# forest21.net
KiCad netlist of a schematic drawn in EAGLE
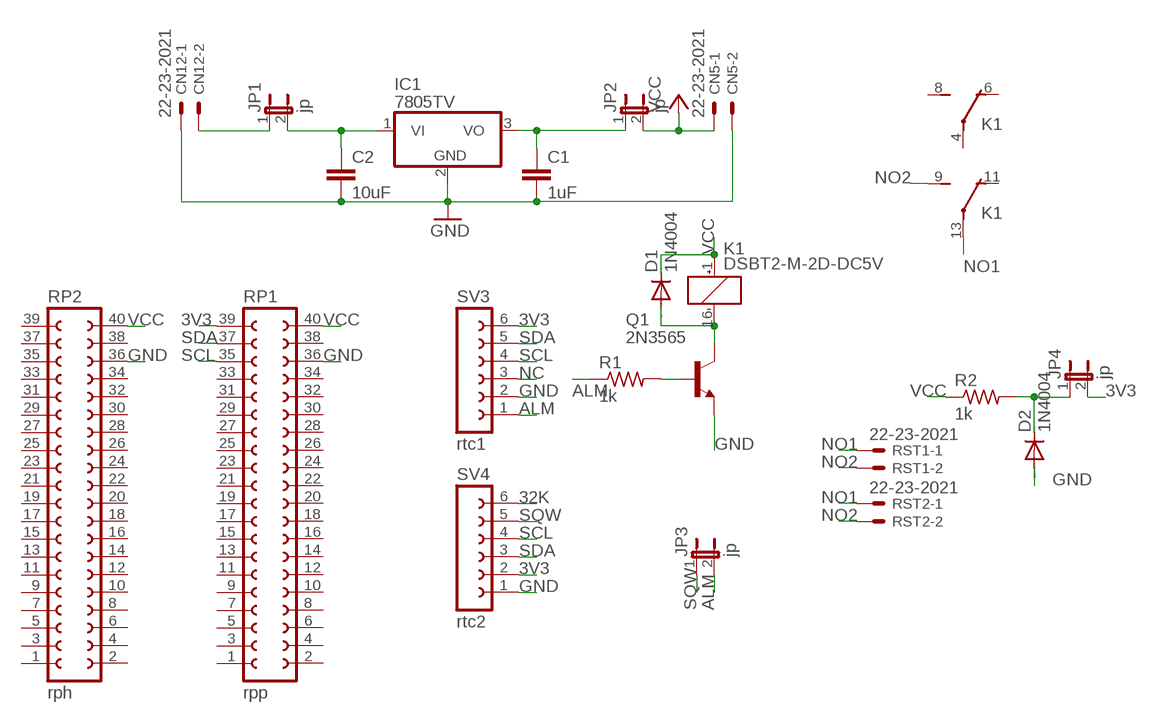
[diagram p0: schematic, sheet 1]

(export (version "E")
  (design (tool "Eeschema 10.0.6"))
  (components
    (comp (ref "C1")
      (value "1uF")
      (footprint "eagle-import:C025-030X050")
      (libsource (lib "eagle-import") (part "C-EU025-030X050"))
    )
    (comp (ref "C2")
      (value "10uF")
      (footprint "eagle-import:C025-030X050")
      (libsource (lib "eagle-import") (part "C-EU025-030X050"))
    )
    (comp (ref "CN5")
      (value "22-23-2021")
      (footprint "eagle-import:22-23-2021")
      (fields (field (name "MF") "MOLEX"))
      (libsource (lib "eagle-import") (part "22-23-2021"))
    )
    (comp (ref "CN12")
      (value "22-23-2021")
      (footprint "eagle-import:22-23-2021")
      (fields (field (name "MF") "MOLEX"))
      (libsource (lib "eagle-import") (part "22-23-2021"))
    )
    (comp (ref "D1")
      (value "1N4004")
      (footprint "eagle-import:DO41-10")
      (libsource (lib "eagle-import") (part "1N4004"))
    )
    (comp (ref "D2")
      (value "1N4004")
      (footprint "eagle-import:DO41-10")
      (libsource (lib "eagle-import") (part "1N4004"))
    )
    (comp (ref "IC1")
      (value "7805TV")
      (footprint "eagle-import:TO220V")
      (libsource (lib "eagle-import") (part "78TV05"))
    )
    (comp (ref "JP1")
      (value "jp")
      (footprint "eagle-import:JP1")
      (libsource (lib "eagle-import") (part "JP1E"))
    )
    (comp (ref "JP2")
      (value "jp")
      (footprint "eagle-import:JP1")
      (libsource (lib "eagle-import") (part "JP1E"))
    )
    (comp (ref "JP3")
      (value "jp")
      (footprint "eagle-import:JP1")
      (libsource (lib "eagle-import") (part "JP1E"))
    )
    (comp (ref "JP4")
      (value "jp")
      (footprint "eagle-import:JP1")
      (libsource (lib "eagle-import") (part "JP1E"))
    )
    (comp (ref "K1")
      (value "DSBT2-M-2D-DC5V")
      (footprint "eagle-import:DS-BT")
      (libsource (lib "eagle-import") (part "DSBT2-M-2D-DC5V"))
    )
    (comp (ref "Q1")
      (value "2N3565")
      (footprint "eagle-import:TO92")
      (libsource (lib "eagle-import") (part "2N3565"))
    )
    (comp (ref "R1")
      (value "1k")
      (footprint "eagle-import:0207_7")
      (libsource (lib "eagle-import") (part "R-US_0207/7"))
    )
    (comp (ref "R2")
      (value "1k")
      (footprint "eagle-import:0207_7")
      (libsource (lib "eagle-import") (part "R-US_0207/7"))
    )
    (comp (ref "RP1")
      (value "rpp")
      (footprint "eagle-import:FE20-2")
      (libsource (lib "eagle-import") (part "FE20-2"))
    )
    (comp (ref "RP2")
      (value "rph")
      (footprint "eagle-import:FE20-2")
      (libsource (lib "eagle-import") (part "FE20-2"))
    )
    (comp (ref "RST1")
      (value "22-23-2021")
      (footprint "eagle-import:22-23-2021")
      (fields (field (name "MF") "MOLEX"))
      (libsource (lib "eagle-import") (part "22-23-2021"))
    )
    (comp (ref "RST2")
      (value "22-23-2021")
      (footprint "eagle-import:22-23-2021")
      (fields (field (name "MF") "MOLEX"))
      (libsource (lib "eagle-import") (part "22-23-2021"))
    )
    (comp (ref "SV3")
      (value "rtc1")
      (footprint "eagle-import:FE06")
      (libsource (lib "eagle-import") (part "FE06-1"))
    )
    (comp (ref "SV4")
      (value "rtc2")
      (footprint "eagle-import:FE06")
      (libsource (lib "eagle-import") (part "FE06-1"))
    )
  )
  (nets
    (net (code "1") (name "/3V3") (class "Default")
      (node (ref "JP4") (pin "2") (pinfunction "2_2") (pintype "passive"))
      (node (ref "RP1") (pin "39") (pinfunction "39_39") (pintype "passive"))
      (node (ref "SV3") (pin "6") (pinfunction "6_6") (pintype "passive"))
      (node (ref "SV4") (pin "2") (pinfunction "2_2") (pintype "passive"))
    )
    (net (code "2") (name "/32K") (class "Default")
      (node (ref "SV4") (pin "6") (pinfunction "6_6") (pintype "passive"))
    )
    (net (code "3") (name "/ALM") (class "Default")
      (node (ref "JP3") (pin "2") (pinfunction "2_2") (pintype "passive"))
      (node (ref "R1") (pin "1") (pinfunction "1_1") (pintype "passive"))
      (node (ref "SV3") (pin "1") (pinfunction "1_1") (pintype "passive"))
    )
    (net (code "4") (name "/NC") (class "Default")
      (node (ref "SV3") (pin "3") (pinfunction "3_3") (pintype "passive"))
    )
    (net (code "5") (name "/NO1") (class "Default")
      (node (ref "K1") (pin "13") (pinfunction "P_13") (pintype "passive"))
      (node (ref "RST1") (pin "1") (pinfunction "S_1") (pintype "passive"))
      (node (ref "RST2") (pin "1") (pinfunction "S_1") (pintype "passive"))
    )
    (net (code "6") (name "/NO2") (class "Default")
      (node (ref "K1") (pin "9") (pinfunction "S_9") (pintype "passive"))
      (node (ref "RST1") (pin "2") (pinfunction "S_2") (pintype "passive"))
      (node (ref "RST2") (pin "2") (pinfunction "S_2") (pintype "passive"))
    )
    (net (code "7") (name "/SCL") (class "Default")
      (node (ref "RP1") (pin "35") (pinfunction "35_35") (pintype "passive"))
      (node (ref "SV3") (pin "4") (pinfunction "4_4") (pintype "passive"))
      (node (ref "SV4") (pin "4") (pinfunction "4_4") (pintype "passive"))
    )
    (net (code "8") (name "/SDA") (class "Default")
      (node (ref "RP1") (pin "37") (pinfunction "37_37") (pintype "passive"))
      (node (ref "SV3") (pin "5") (pinfunction "5_5") (pintype "passive"))
      (node (ref "SV4") (pin "3") (pinfunction "3_3") (pintype "passive"))
    )
    (net (code "9") (name "/SQW") (class "Default")
      (node (ref "JP3") (pin "1") (pinfunction "1_1") (pintype "passive"))
      (node (ref "SV4") (pin "5") (pinfunction "5_5") (pintype "passive"))
    )
    (net (code "10") (name "GND") (class "Default")
      (node (ref "C1") (pin "2") (pinfunction "2_2") (pintype "passive"))
      (node (ref "C2") (pin "2") (pinfunction "2_2") (pintype "passive"))
      (node (ref "CN12") (pin "1") (pinfunction "S_1") (pintype "passive"))
      (node (ref "CN5") (pin "2") (pinfunction "S_2") (pintype "passive"))
      (node (ref "D2") (pin "A") (pinfunction "A_A") (pintype "passive"))
      (node (ref "IC1") (pin "2") (pinfunction "GND_2") (pintype "passive"))
      (node (ref "Q1") (pin "3") (pinfunction "E_3") (pintype "passive"))
      (node (ref "RP1") (pin "36") (pinfunction "36_36") (pintype "passive"))
      (node (ref "RP2") (pin "36") (pinfunction "36_36") (pintype "passive"))
      (node (ref "SV3") (pin "2") (pinfunction "2_2") (pintype "passive"))
      (node (ref "SV4") (pin "1") (pinfunction "1_1") (pintype "passive"))
    )
    (net (code "11") (name "Net-(CN12B-S)") (class "Default")
      (node (ref "CN12") (pin "2") (pinfunction "S_2") (pintype "passive"))
      (node (ref "JP1") (pin "1") (pinfunction "1_1") (pintype "passive"))
    )
    (net (code "12") (name "Net-(D2-PadC)") (class "Default")
      (node (ref "D2") (pin "C") (pinfunction "C_C") (pintype "passive"))
      (node (ref "JP4") (pin "1") (pinfunction "1_1") (pintype "passive"))
      (node (ref "R2") (pin "2") (pinfunction "2_2") (pintype "passive"))
    )
    (net (code "13") (name "Net-(IC1-VI)") (class "Default")
      (node (ref "C2") (pin "1") (pinfunction "1_1") (pintype "passive"))
      (node (ref "IC1") (pin "1") (pinfunction "VI_1") (pintype "input"))
      (node (ref "JP1") (pin "2") (pinfunction "2_2") (pintype "passive"))
    )
    (net (code "14") (name "Net-(IC1-VO)") (class "Default")
      (node (ref "C1") (pin "1") (pinfunction "1_1") (pintype "passive"))
      (node (ref "IC1") (pin "3") (pinfunction "VO_3") (pintype "passive"))
      (node (ref "JP2") (pin "1") (pinfunction "1_1") (pintype "passive"))
    )
    (net (code "15") (name "Net-(K1A--)") (class "Default")
      (node (ref "D1") (pin "A") (pinfunction "A_A") (pintype "passive"))
      (node (ref "K1") (pin "16") (pinfunction "-_16") (pintype "passive"))
      (node (ref "Q1") (pin "1") (pinfunction "C_1") (pintype "passive"))
    )
    (net (code "16") (name "Net-(Q1-B)") (class "Default")
      (node (ref "Q1") (pin "2") (pinfunction "B_2") (pintype "passive"))
      (node (ref "R1") (pin "2") (pinfunction "2_2") (pintype "passive"))
    )
    (net (code "17") (name "VCC") (class "Default")
      (node (ref "CN5") (pin "1") (pinfunction "S_1") (pintype "passive"))
      (node (ref "D1") (pin "C") (pinfunction "C_C") (pintype "passive"))
      (node (ref "JP2") (pin "2") (pinfunction "2_2") (pintype "passive"))
      (node (ref "K1") (pin "1") (pinfunction "+_1") (pintype "passive"))
      (node (ref "R2") (pin "1") (pinfunction "1_1") (pintype "passive"))
      (node (ref "RP1") (pin "40") (pinfunction "40_40") (pintype "passive"))
      (node (ref "RP2") (pin "40") (pinfunction "40_40") (pintype "passive"))
    )
    (net (code "18") (name "unconnected-(K1B-O-Pad6)") (class "Default")
      (node (ref "K1") (pin "6") (pinfunction "O_6") (pintype "passive"))
    )
    (net (code "19") (name "unconnected-(K1B-P-Pad4)") (class "Default")
      (node (ref "K1") (pin "4") (pinfunction "P_4") (pintype "passive"))
    )
    (net (code "20") (name "unconnected-(K1B-S-Pad8)") (class "Default")
      (node (ref "K1") (pin "8") (pinfunction "S_8") (pintype "passive"))
    )
    (net (code "21") (name "unconnected-(K1C-O-Pad11)") (class "Default")
      (node (ref "K1") (pin "11") (pinfunction "O_11") (pintype "passive"))
    )
    (net (code "22") (name "unconnected-(RP1-Pad1)") (class "Default")
      (node (ref "RP1") (pin "1") (pinfunction "1_1") (pintype "passive"))
    )
    (net (code "23") (name "unconnected-(RP1-Pad2)") (class "Default")
      (node (ref "RP1") (pin "2") (pinfunction "2_2") (pintype "passive"))
    )
    (net (code "24") (name "unconnected-(RP1-Pad3)") (class "Default")
      (node (ref "RP1") (pin "3") (pinfunction "3_3") (pintype "passive"))
    )
    (net (code "25") (name "unconnected-(RP1-Pad4)") (class "Default")
      (node (ref "RP1") (pin "4") (pinfunction "4_4") (pintype "passive"))
    )
    (net (code "26") (name "unconnected-(RP1-Pad5)") (class "Default")
      (node (ref "RP1") (pin "5") (pinfunction "5_5") (pintype "passive"))
    )
    (net (code "27") (name "unconnected-(RP1-Pad6)") (class "Default")
      (node (ref "RP1") (pin "6") (pinfunction "6_6") (pintype "passive"))
    )
    (net (code "28") (name "unconnected-(RP1-Pad7)") (class "Default")
      (node (ref "RP1") (pin "7") (pinfunction "7_7") (pintype "passive"))
    )
    (net (code "29") (name "unconnected-(RP1-Pad8)") (class "Default")
      (node (ref "RP1") (pin "8") (pinfunction "8_8") (pintype "passive"))
    )
    (net (code "30") (name "unconnected-(RP1-Pad9)") (class "Default")
      (node (ref "RP1") (pin "9") (pinfunction "9_9") (pintype "passive"))
    )
    (net (code "31") (name "unconnected-(RP1-Pad10)") (class "Default")
      (node (ref "RP1") (pin "10") (pinfunction "10_10") (pintype "passive"))
    )
    (net (code "32") (name "unconnected-(RP1-Pad11)") (class "Default")
      (node (ref "RP1") (pin "11") (pinfunction "11_11") (pintype "passive"))
    )
    (net (code "33") (name "unconnected-(RP1-Pad12)") (class "Default")
      (node (ref "RP1") (pin "12") (pinfunction "12_12") (pintype "passive"))
    )
    (net (code "34") (name "unconnected-(RP1-Pad13)") (class "Default")
      (node (ref "RP1") (pin "13") (pinfunction "13_13") (pintype "passive"))
    )
    (net (code "35") (name "unconnected-(RP1-Pad14)") (class "Default")
      (node (ref "RP1") (pin "14") (pinfunction "14_14") (pintype "passive"))
    )
    (net (code "36") (name "unconnected-(RP1-Pad15)") (class "Default")
      (node (ref "RP1") (pin "15") (pinfunction "15_15") (pintype "passive"))
    )
    (net (code "37") (name "unconnected-(RP1-Pad16)") (class "Default")
      (node (ref "RP1") (pin "16") (pinfunction "16_16") (pintype "passive"))
    )
    (net (code "38") (name "unconnected-(RP1-Pad17)") (class "Default")
      (node (ref "RP1") (pin "17") (pinfunction "17_17") (pintype "passive"))
    )
    (net (code "39") (name "unconnected-(RP1-Pad18)") (class "Default")
      (node (ref "RP1") (pin "18") (pinfunction "18_18") (pintype "passive"))
    )
    (net (code "40") (name "unconnected-(RP1-Pad19)") (class "Default")
      (node (ref "RP1") (pin "19") (pinfunction "19_19") (pintype "passive"))
    )
    (net (code "41") (name "unconnected-(RP1-Pad20)") (class "Default")
      (node (ref "RP1") (pin "20") (pinfunction "20_20") (pintype "passive"))
    )
    (net (code "42") (name "unconnected-(RP1-Pad21)") (class "Default")
      (node (ref "RP1") (pin "21") (pinfunction "21_21") (pintype "passive"))
    )
    (net (code "43") (name "unconnected-(RP1-Pad22)") (class "Default")
      (node (ref "RP1") (pin "22") (pinfunction "22_22") (pintype "passive"))
    )
    (net (code "44") (name "unconnected-(RP1-Pad23)") (class "Default")
      (node (ref "RP1") (pin "23") (pinfunction "23_23") (pintype "passive"))
    )
    (net (code "45") (name "unconnected-(RP1-Pad24)") (class "Default")
      (node (ref "RP1") (pin "24") (pinfunction "24_24") (pintype "passive"))
    )
    (net (code "46") (name "unconnected-(RP1-Pad25)") (class "Default")
      (node (ref "RP1") (pin "25") (pinfunction "25_25") (pintype "passive"))
    )
    (net (code "47") (name "unconnected-(RP1-Pad26)") (class "Default")
      (node (ref "RP1") (pin "26") (pinfunction "26_26") (pintype "passive"))
    )
    (net (code "48") (name "unconnected-(RP1-Pad27)") (class "Default")
      (node (ref "RP1") (pin "27") (pinfunction "27_27") (pintype "passive"))
    )
    (net (code "49") (name "unconnected-(RP1-Pad28)") (class "Default")
      (node (ref "RP1") (pin "28") (pinfunction "28_28") (pintype "passive"))
    )
    (net (code "50") (name "unconnected-(RP1-Pad29)") (class "Default")
      (node (ref "RP1") (pin "29") (pinfunction "29_29") (pintype "passive"))
    )
    (net (code "51") (name "unconnected-(RP1-Pad30)") (class "Default")
      (node (ref "RP1") (pin "30") (pinfunction "30_30") (pintype "passive"))
    )
    (net (code "52") (name "unconnected-(RP1-Pad31)") (class "Default")
      (node (ref "RP1") (pin "31") (pinfunction "31_31") (pintype "passive"))
    )
    (net (code "53") (name "unconnected-(RP1-Pad32)") (class "Default")
      (node (ref "RP1") (pin "32") (pinfunction "32_32") (pintype "passive"))
    )
    (net (code "54") (name "unconnected-(RP1-Pad33)") (class "Default")
      (node (ref "RP1") (pin "33") (pinfunction "33_33") (pintype "passive"))
    )
    (net (code "55") (name "unconnected-(RP1-Pad34)") (class "Default")
      (node (ref "RP1") (pin "34") (pinfunction "34_34") (pintype "passive"))
    )
    (net (code "56") (name "unconnected-(RP1-Pad38)") (class "Default")
      (node (ref "RP1") (pin "38") (pinfunction "38_38") (pintype "passive"))
    )
    (net (code "57") (name "unconnected-(RP2-Pad1)") (class "Default")
      (node (ref "RP2") (pin "1") (pinfunction "1_1") (pintype "passive"))
    )
    (net (code "58") (name "unconnected-(RP2-Pad2)") (class "Default")
      (node (ref "RP2") (pin "2") (pinfunction "2_2") (pintype "passive"))
    )
    (net (code "59") (name "unconnected-(RP2-Pad3)") (class "Default")
      (node (ref "RP2") (pin "3") (pinfunction "3_3") (pintype "passive"))
    )
    (net (code "60") (name "unconnected-(RP2-Pad4)") (class "Default")
      (node (ref "RP2") (pin "4") (pinfunction "4_4") (pintype "passive"))
    )
    (net (code "61") (name "unconnected-(RP2-Pad5)") (class "Default")
      (node (ref "RP2") (pin "5") (pinfunction "5_5") (pintype "passive"))
    )
    (net (code "62") (name "unconnected-(RP2-Pad6)") (class "Default")
      (node (ref "RP2") (pin "6") (pinfunction "6_6") (pintype "passive"))
    )
    (net (code "63") (name "unconnected-(RP2-Pad7)") (class "Default")
      (node (ref "RP2") (pin "7") (pinfunction "7_7") (pintype "passive"))
    )
    (net (code "64") (name "unconnected-(RP2-Pad8)") (class "Default")
      (node (ref "RP2") (pin "8") (pinfunction "8_8") (pintype "passive"))
    )
    (net (code "65") (name "unconnected-(RP2-Pad9)") (class "Default")
      (node (ref "RP2") (pin "9") (pinfunction "9_9") (pintype "passive"))
    )
    (net (code "66") (name "unconnected-(RP2-Pad10)") (class "Default")
      (node (ref "RP2") (pin "10") (pinfunction "10_10") (pintype "passive"))
    )
    (net (code "67") (name "unconnected-(RP2-Pad11)") (class "Default")
      (node (ref "RP2") (pin "11") (pinfunction "11_11") (pintype "passive"))
    )
    (net (code "68") (name "unconnected-(RP2-Pad12)") (class "Default")
      (node (ref "RP2") (pin "12") (pinfunction "12_12") (pintype "passive"))
    )
    (net (code "69") (name "unconnected-(RP2-Pad13)") (class "Default")
      (node (ref "RP2") (pin "13") (pinfunction "13_13") (pintype "passive"))
    )
    (net (code "70") (name "unconnected-(RP2-Pad14)") (class "Default")
      (node (ref "RP2") (pin "14") (pinfunction "14_14") (pintype "passive"))
    )
    (net (code "71") (name "unconnected-(RP2-Pad15)") (class "Default")
      (node (ref "RP2") (pin "15") (pinfunction "15_15") (pintype "passive"))
    )
    (net (code "72") (name "unconnected-(RP2-Pad16)") (class "Default")
      (node (ref "RP2") (pin "16") (pinfunction "16_16") (pintype "passive"))
    )
    (net (code "73") (name "unconnected-(RP2-Pad17)") (class "Default")
      (node (ref "RP2") (pin "17") (pinfunction "17_17") (pintype "passive"))
    )
    (net (code "74") (name "unconnected-(RP2-Pad18)") (class "Default")
      (node (ref "RP2") (pin "18") (pinfunction "18_18") (pintype "passive"))
    )
    (net (code "75") (name "unconnected-(RP2-Pad19)") (class "Default")
      (node (ref "RP2") (pin "19") (pinfunction "19_19") (pintype "passive"))
    )
    (net (code "76") (name "unconnected-(RP2-Pad20)") (class "Default")
      (node (ref "RP2") (pin "20") (pinfunction "20_20") (pintype "passive"))
    )
    (net (code "77") (name "unconnected-(RP2-Pad21)") (class "Default")
      (node (ref "RP2") (pin "21") (pinfunction "21_21") (pintype "passive"))
    )
    (net (code "78") (name "unconnected-(RP2-Pad22)") (class "Default")
      (node (ref "RP2") (pin "22") (pinfunction "22_22") (pintype "passive"))
    )
    (net (code "79") (name "unconnected-(RP2-Pad23)") (class "Default")
      (node (ref "RP2") (pin "23") (pinfunction "23_23") (pintype "passive"))
    )
    (net (code "80") (name "unconnected-(RP2-Pad24)") (class "Default")
      (node (ref "RP2") (pin "24") (pinfunction "24_24") (pintype "passive"))
    )
    (net (code "81") (name "unconnected-(RP2-Pad25)") (class "Default")
      (node (ref "RP2") (pin "25") (pinfunction "25_25") (pintype "passive"))
    )
    (net (code "82") (name "unconnected-(RP2-Pad26)") (class "Default")
      (node (ref "RP2") (pin "26") (pinfunction "26_26") (pintype "passive"))
    )
    (net (code "83") (name "unconnected-(RP2-Pad27)") (class "Default")
      (node (ref "RP2") (pin "27") (pinfunction "27_27") (pintype "passive"))
    )
    (net (code "84") (name "unconnected-(RP2-Pad28)") (class "Default")
      (node (ref "RP2") (pin "28") (pinfunction "28_28") (pintype "passive"))
    )
    (net (code "85") (name "unconnected-(RP2-Pad29)") (class "Default")
      (node (ref "RP2") (pin "29") (pinfunction "29_29") (pintype "passive"))
    )
    (net (code "86") (name "unconnected-(RP2-Pad30)") (class "Default")
      (node (ref "RP2") (pin "30") (pinfunction "30_30") (pintype "passive"))
    )
    (net (code "87") (name "unconnected-(RP2-Pad31)") (class "Default")
      (node (ref "RP2") (pin "31") (pinfunction "31_31") (pintype "passive"))
    )
    (net (code "88") (name "unconnected-(RP2-Pad32)") (class "Default")
      (node (ref "RP2") (pin "32") (pinfunction "32_32") (pintype "passive"))
    )
    (net (code "89") (name "unconnected-(RP2-Pad33)") (class "Default")
      (node (ref "RP2") (pin "33") (pinfunction "33_33") (pintype "passive"))
    )
    (net (code "90") (name "unconnected-(RP2-Pad34)") (class "Default")
      (node (ref "RP2") (pin "34") (pinfunction "34_34") (pintype "passive"))
    )
    (net (code "91") (name "unconnected-(RP2-Pad35)") (class "Default")
      (node (ref "RP2") (pin "35") (pinfunction "35_35") (pintype "passive"))
    )
    (net (code "92") (name "unconnected-(RP2-Pad37)") (class "Default")
      (node (ref "RP2") (pin "37") (pinfunction "37_37") (pintype "passive"))
    )
    (net (code "93") (name "unconnected-(RP2-Pad38)") (class "Default")
      (node (ref "RP2") (pin "38") (pinfunction "38_38") (pintype "passive"))
    )
    (net (code "94") (name "unconnected-(RP2-Pad39)") (class "Default")
      (node (ref "RP2") (pin "39") (pinfunction "39_39") (pintype "passive"))
    )
  )
)
